# Power.net
KiCad netlist of a schematic drawn in Altium Designer
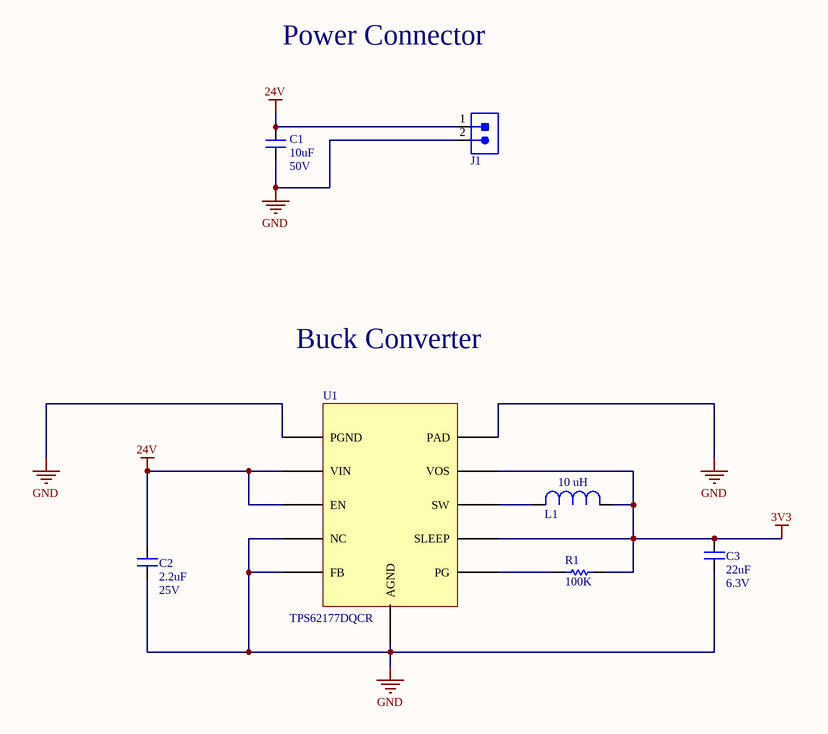
[diagram p0: Power.SchDoc]

(export (version "E")
  (design (tool "Eeschema 10.0.6"))
  (components
    (comp (ref "C1")
      (value "10uF")
      (footprint "CAPC1206(3216)")
      (description "CAP CER 10UF 50V X5R 1206")
      (fields (field (name "VOLTAGE RATING") "50V"))
      (libsource (lib "UWRT_Schematic_Library_2020") (part "CAP_10uF_50V_1206"))
    )
    (comp (ref "C2")
      (value "2.2uF")
      (footprint "CAPC2012X140N")
      (description "CAP CER 2.2UF 25V X7R 0805")
      (fields
        (field (name "TOLERANCE") "10%")
        (field (name "VOLTAGE RATING") "25V")
        (field (name "Comment") "CAP_2.2uF_25V_0805")
      )
      (libsource (lib "UWRT_Schematic_Library_2020") (part "CAP_2.2uF_25V_0805"))
    )
    (comp (ref "C3")
      (value "22uF")
      (footprint "CAPC0603(1608)55_N")
      (description "CAP CER 22UF 6.3V X5R 0805")
      (fields
        (field (name "TOLERANCE") "20%")
        (field (name "VOLTAGE RATING") "6.3V")
        (field (name "Comment") "CAP_22uF_6.3V_0805")
      )
      (libsource (lib "UWRT_Schematic_Library_2020") (part "CAP_22uF_6.3V_0805"))
    )
    (comp (ref "J1")
      (value "CON_2M_TERM")
      (footprint "1935161")
      (description "TERM BLK 2POS SIDE ENTRY 5MM")
      (fields (field (name "VOLTAGE") "300V"))
      (libsource (lib "UWRT_Schematic_Library_2020") (part "CON_2M_TERM"))
    )
    (comp (ref "L1")
      (value "IND_10uH_6045")
      (footprint "IND_BOURNS_SRN6045")
      (description "IND WIRE 10 UH 6045")
      (libsource (lib "UWRT_Schematic_Library_2020") (part "IND_10uH_6045"))
    )
    (comp (ref "R1")
      (value "100K")
      (footprint "RESC0603(1608)_N")
      (description "RES SMD 100K OHM 5% 1/10W 0603")
      (fields (field (name "TOLERANCE") "5%") (field (name "Comment") "RES_100K_0603"))
      (libsource (lib "UWRT_Schematic_Library_2020") (part "RES_100K_0603"))
    )
    (comp (ref "U1")
      (value "TPS62177DQCR")
      (footprint "DQC0010A")
      (description "IC REG BUCK 3.3V 500MA 10WSON")
      (libsource (lib "UWRT_Schematic_Library_2020") (part "TPS62177DQCR"))
    )
  )
  (nets
    (net (code "1") (name "3V3") (class "Default")
      (node (ref "C3") (pin "2") (pinfunction "2_2") (pintype "passive"))
      (node (ref "L1") (pin "2") (pinfunction "2_2") (pintype "passive"))
      (node (ref "R1") (pin "1") (pinfunction "1_1") (pintype "passive"))
      (node (ref "U1") (pin "10") (pinfunction "VOS_10") (pintype "passive"))
      (node (ref "U1") (pin "8") (pinfunction "SLEEP_8") (pintype "passive"))
    )
    (net (code "2") (name "24V") (class "Default")
      (node (ref "C1") (pin "2") (pinfunction "2_2") (pintype "passive"))
      (node (ref "C2") (pin "2") (pinfunction "2_2") (pintype "passive"))
      (node (ref "J1") (pin "1") (pinfunction "1_1") (pintype "passive"))
      (node (ref "U1") (pin "2") (pinfunction "VIN_2") (pintype "passive"))
      (node (ref "U1") (pin "3") (pinfunction "EN_3") (pintype "passive"))
    )
    (net (code "3") (name "GND") (class "Default")
      (node (ref "C1") (pin "1") (pinfunction "1_1") (pintype "passive"))
      (node (ref "C2") (pin "1") (pinfunction "1_1") (pintype "passive"))
      (node (ref "C3") (pin "1") (pinfunction "1_1") (pintype "passive"))
      (node (ref "J1") (pin "2") (pinfunction "2_2") (pintype "passive"))
      (node (ref "U1") (pin "1") (pinfunction "PGND_1") (pintype "passive"))
      (node (ref "U1") (pin "11") (pinfunction "PAD_11") (pintype "passive"))
      (node (ref "U1") (pin "4") (pinfunction "NC_4") (pintype "passive"))
      (node (ref "U1") (pin "5") (pinfunction "FB_5") (pintype "passive"))
      (node (ref "U1") (pin "6") (pinfunction "AGND_6") (pintype "passive"))
    )
    (net (code "4") (name "Net-(U1-PG)") (class "Default")
      (node (ref "R1") (pin "2") (pinfunction "2_2") (pintype "passive"))
      (node (ref "U1") (pin "7") (pinfunction "PG_7") (pintype "passive"))
    )
    (net (code "5") (name "Net-(U1-SW)") (class "Default")
      (node (ref "L1") (pin "1") (pinfunction "1_1") (pintype "passive"))
      (node (ref "U1") (pin "9") (pinfunction "SW_9") (pintype "passive"))
    )
  )
)
